# board.net
KiCad netlist of a schematic drawn in EAGLE
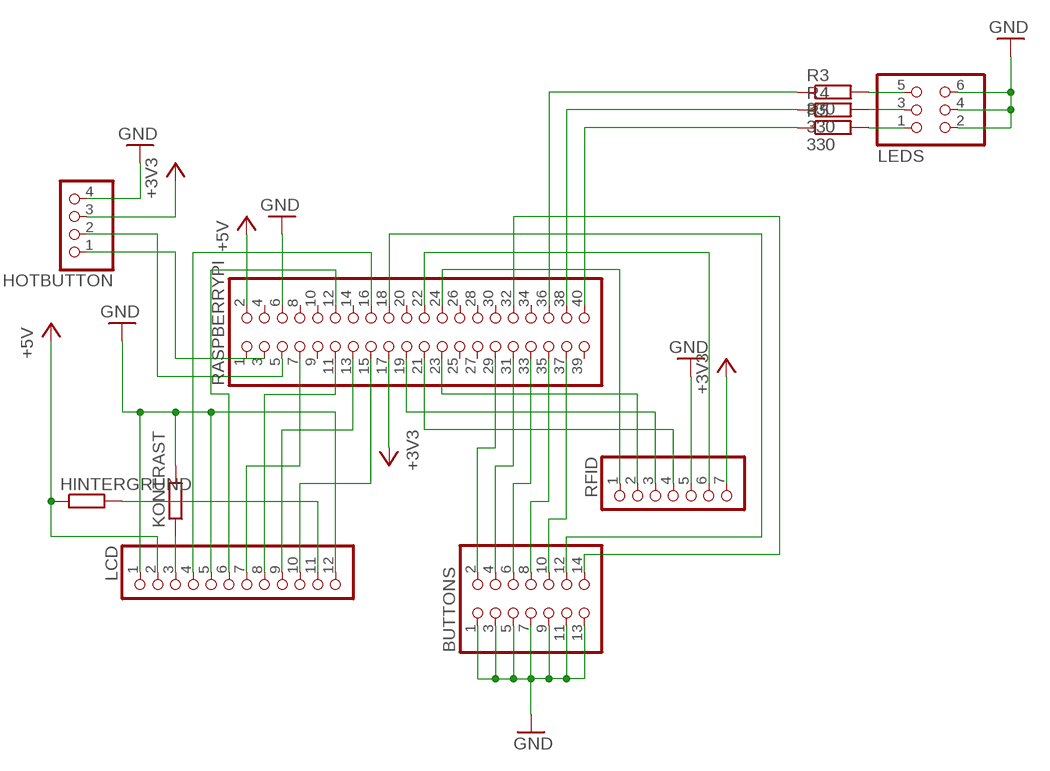
[diagram p0: schematic, sheet 1]

(export (version "E")
  (design (tool "Eeschema 10.0.6"))
  (components
    (comp (ref "BUTTONS")
      (value "PINHD-2X7")
      (footprint "eagle-import:2X07")
      (libsource (lib "eagle-import") (part "PINHD-2X7"))
    )
    (comp (ref "HINTERGRUND")
      (value "R-EU_0207/10")
      (footprint "eagle-import:0207_10")
      (libsource (lib "eagle-import") (part "R-EU_0207/10"))
    )
    (comp (ref "HOTBUTTON")
      (value "PINHD-1X4")
      (footprint "eagle-import:1X04")
      (libsource (lib "eagle-import") (part "PINHD-1X4"))
    )
    (comp (ref "KONTRAST")
      (value "R-EU_0207/10")
      (footprint "eagle-import:0207_10")
      (libsource (lib "eagle-import") (part "R-EU_0207/10"))
    )
    (comp (ref "LCD")
      (value "PINHD-1X12")
      (footprint "eagle-import:1X12")
      (libsource (lib "eagle-import") (part "PINHD-1X12"))
    )
    (comp (ref "LEDS")
      (value "PINHD-2X3")
      (footprint "eagle-import:2X03")
      (libsource (lib "eagle-import") (part "PINHD-2X3"))
    )
    (comp (ref "R3")
      (value "330")
      (footprint "eagle-import:0207_10")
      (libsource (lib "eagle-import") (part "R-EU_0207/10"))
    )
    (comp (ref "R4")
      (value "330")
      (footprint "eagle-import:0207_10")
      (libsource (lib "eagle-import") (part "R-EU_0207/10"))
    )
    (comp (ref "R5")
      (value "330")
      (footprint "eagle-import:0207_10")
      (libsource (lib "eagle-import") (part "R-EU_0207/10"))
    )
    (comp (ref "RASPBERRYPI")
      (value "PINHD-2X20")
      (footprint "eagle-import:2X20")
      (libsource (lib "eagle-import") (part "PINHD-2X20"))
    )
    (comp (ref "RFID")
      (value "PINHD-1X7")
      (footprint "eagle-import:1X07")
      (libsource (lib "eagle-import") (part "PINHD-1X7"))
    )
  )
  (nets
    (net (code "1") (name "+3V3") (class "Default")
      (node (ref "HOTBUTTON") (pin "3") (pinfunction "3_3") (pintype "passive"))
      (node (ref "RASPBERRYPI") (pin "17") (pinfunction "17_17") (pintype "passive"))
      (node (ref "RFID") (pin "7") (pinfunction "7_7") (pintype "passive"))
    )
    (net (code "2") (name "+5V") (class "Default")
      (node (ref "HINTERGRUND") (pin "1") (pinfunction "1_1") (pintype "passive"))
      (node (ref "LCD") (pin "2") (pinfunction "2_2") (pintype "passive"))
      (node (ref "RASPBERRYPI") (pin "2") (pinfunction "2_2") (pintype "passive"))
    )
    (net (code "3") (name "GND") (class "Default")
      (node (ref "BUTTONS") (pin "1") (pinfunction "1_1") (pintype "passive"))
      (node (ref "BUTTONS") (pin "11") (pinfunction "11_11") (pintype "passive"))
      (node (ref "BUTTONS") (pin "13") (pinfunction "13_13") (pintype "passive"))
      (node (ref "BUTTONS") (pin "3") (pinfunction "3_3") (pintype "passive"))
      (node (ref "BUTTONS") (pin "5") (pinfunction "5_5") (pintype "passive"))
      (node (ref "BUTTONS") (pin "7") (pinfunction "7_7") (pintype "passive"))
      (node (ref "BUTTONS") (pin "9") (pinfunction "9_9") (pintype "passive"))
      (node (ref "HOTBUTTON") (pin "4") (pinfunction "4_4") (pintype "passive"))
      (node (ref "KONTRAST") (pin "2") (pinfunction "2_2") (pintype "passive"))
      (node (ref "LCD") (pin "1") (pinfunction "1_1") (pintype "passive"))
      (node (ref "LCD") (pin "12") (pinfunction "12_12") (pintype "passive"))
      (node (ref "LCD") (pin "5") (pinfunction "5_5") (pintype "passive"))
      (node (ref "LEDS") (pin "2") (pinfunction "2_2") (pintype "passive"))
      (node (ref "LEDS") (pin "4") (pinfunction "4_4") (pintype "passive"))
      (node (ref "LEDS") (pin "6") (pinfunction "6_6") (pintype "passive"))
      (node (ref "RASPBERRYPI") (pin "6") (pinfunction "6_6") (pintype "passive"))
      (node (ref "RFID") (pin "5") (pinfunction "5_5") (pintype "passive"))
    )
    (net (code "4") (name "Net-(BUTTONS-Pad2)") (class "Default")
      (node (ref "BUTTONS") (pin "2") (pinfunction "2_2") (pintype "passive"))
      (node (ref "RASPBERRYPI") (pin "29") (pinfunction "29_29") (pintype "passive"))
    )
    (net (code "5") (name "Net-(BUTTONS-Pad4)") (class "Default")
      (node (ref "BUTTONS") (pin "4") (pinfunction "4_4") (pintype "passive"))
      (node (ref "RASPBERRYPI") (pin "31") (pinfunction "31_31") (pintype "passive"))
    )
    (net (code "6") (name "Net-(BUTTONS-Pad6)") (class "Default")
      (node (ref "BUTTONS") (pin "6") (pinfunction "6_6") (pintype "passive"))
      (node (ref "RASPBERRYPI") (pin "33") (pinfunction "33_33") (pintype "passive"))
    )
    (net (code "7") (name "Net-(BUTTONS-Pad8)") (class "Default")
      (node (ref "BUTTONS") (pin "8") (pinfunction "8_8") (pintype "passive"))
      (node (ref "RASPBERRYPI") (pin "35") (pinfunction "35_35") (pintype "passive"))
    )
    (net (code "8") (name "Net-(BUTTONS-Pad10)") (class "Default")
      (node (ref "BUTTONS") (pin "10") (pinfunction "10_10") (pintype "passive"))
      (node (ref "RASPBERRYPI") (pin "37") (pinfunction "37_37") (pintype "passive"))
    )
    (net (code "9") (name "Net-(BUTTONS-Pad12)") (class "Default")
      (node (ref "BUTTONS") (pin "12") (pinfunction "12_12") (pintype "passive"))
      (node (ref "RASPBERRYPI") (pin "18") (pinfunction "18_18") (pintype "passive"))
    )
    (net (code "10") (name "Net-(BUTTONS-Pad14)") (class "Default")
      (node (ref "BUTTONS") (pin "14") (pinfunction "14_14") (pintype "passive"))
      (node (ref "RASPBERRYPI") (pin "32") (pinfunction "32_32") (pintype "passive"))
    )
    (net (code "11") (name "Net-(HINTERGRUND-Pad2)") (class "Default")
      (node (ref "HINTERGRUND") (pin "2") (pinfunction "2_2") (pintype "passive"))
      (node (ref "LCD") (pin "11") (pinfunction "11_11") (pintype "passive"))
    )
    (net (code "12") (name "Net-(HOTBUTTON-Pad1)") (class "Default")
      (node (ref "HOTBUTTON") (pin "1") (pinfunction "1_1") (pintype "passive"))
      (node (ref "RASPBERRYPI") (pin "3") (pinfunction "3_3") (pintype "passive"))
    )
    (net (code "13") (name "Net-(HOTBUTTON-Pad2)") (class "Default")
      (node (ref "HOTBUTTON") (pin "2") (pinfunction "2_2") (pintype "passive"))
      (node (ref "RASPBERRYPI") (pin "5") (pinfunction "5_5") (pintype "passive"))
    )
    (net (code "14") (name "Net-(KONTRAST-Pad1)") (class "Default")
      (node (ref "KONTRAST") (pin "1") (pinfunction "1_1") (pintype "passive"))
      (node (ref "LCD") (pin "3") (pinfunction "3_3") (pintype "passive"))
    )
    (net (code "15") (name "Net-(LCD-Pad4)") (class "Default")
      (node (ref "LCD") (pin "4") (pinfunction "4_4") (pintype "passive"))
      (node (ref "RASPBERRYPI") (pin "16") (pinfunction "16_16") (pintype "passive"))
    )
    (net (code "16") (name "Net-(LCD-Pad6)") (class "Default")
      (node (ref "LCD") (pin "6") (pinfunction "6_6") (pintype "passive"))
      (node (ref "RASPBERRYPI") (pin "12") (pinfunction "12_12") (pintype "passive"))
    )
    (net (code "17") (name "Net-(LCD-Pad7)") (class "Default")
      (node (ref "LCD") (pin "7") (pinfunction "7_7") (pintype "passive"))
      (node (ref "RASPBERRYPI") (pin "7") (pinfunction "7_7") (pintype "passive"))
    )
    (net (code "18") (name "Net-(LCD-Pad8)") (class "Default")
      (node (ref "LCD") (pin "8") (pinfunction "8_8") (pintype "passive"))
      (node (ref "RASPBERRYPI") (pin "11") (pinfunction "11_11") (pintype "passive"))
    )
    (net (code "19") (name "Net-(LCD-Pad9)") (class "Default")
      (node (ref "LCD") (pin "9") (pinfunction "9_9") (pintype "passive"))
      (node (ref "RASPBERRYPI") (pin "13") (pinfunction "13_13") (pintype "passive"))
    )
    (net (code "20") (name "Net-(LCD-Pad10)") (class "Default")
      (node (ref "LCD") (pin "10") (pinfunction "10_10") (pintype "passive"))
      (node (ref "RASPBERRYPI") (pin "15") (pinfunction "15_15") (pintype "passive"))
    )
    (net (code "21") (name "Net-(LEDS-Pad1)") (class "Default")
      (node (ref "LEDS") (pin "1") (pinfunction "1_1") (pintype "passive"))
      (node (ref "R5") (pin "2") (pinfunction "2_2") (pintype "passive"))
    )
    (net (code "22") (name "Net-(LEDS-Pad3)") (class "Default")
      (node (ref "LEDS") (pin "3") (pinfunction "3_3") (pintype "passive"))
      (node (ref "R4") (pin "2") (pinfunction "2_2") (pintype "passive"))
    )
    (net (code "23") (name "Net-(LEDS-Pad5)") (class "Default")
      (node (ref "LEDS") (pin "5") (pinfunction "5_5") (pintype "passive"))
      (node (ref "R3") (pin "2") (pinfunction "2_2") (pintype "passive"))
    )
    (net (code "24") (name "Net-(R3-Pad1)") (class "Default")
      (node (ref "R3") (pin "1") (pinfunction "1_1") (pintype "passive"))
      (node (ref "RASPBERRYPI") (pin "36") (pinfunction "36_36") (pintype "passive"))
    )
    (net (code "25") (name "Net-(R4-Pad1)") (class "Default")
      (node (ref "R4") (pin "1") (pinfunction "1_1") (pintype "passive"))
      (node (ref "RASPBERRYPI") (pin "38") (pinfunction "38_38") (pintype "passive"))
    )
    (net (code "26") (name "Net-(R5-Pad1)") (class "Default")
      (node (ref "R5") (pin "1") (pinfunction "1_1") (pintype "passive"))
      (node (ref "RASPBERRYPI") (pin "40") (pinfunction "40_40") (pintype "passive"))
    )
    (net (code "27") (name "Net-(RASPBERRYPI-Pad19)") (class "Default")
      (node (ref "RASPBERRYPI") (pin "19") (pinfunction "19_19") (pintype "passive"))
      (node (ref "RFID") (pin "3") (pinfunction "3_3") (pintype "passive"))
    )
    (net (code "28") (name "Net-(RASPBERRYPI-Pad21)") (class "Default")
      (node (ref "RASPBERRYPI") (pin "21") (pinfunction "21_21") (pintype "passive"))
      (node (ref "RFID") (pin "4") (pinfunction "4_4") (pintype "passive"))
    )
    (net (code "29") (name "Net-(RASPBERRYPI-Pad22)") (class "Default")
      (node (ref "RASPBERRYPI") (pin "22") (pinfunction "22_22") (pintype "passive"))
      (node (ref "RFID") (pin "6") (pinfunction "6_6") (pintype "passive"))
    )
    (net (code "30") (name "Net-(RASPBERRYPI-Pad23)") (class "Default")
      (node (ref "RASPBERRYPI") (pin "23") (pinfunction "23_23") (pintype "passive"))
      (node (ref "RFID") (pin "2") (pinfunction "2_2") (pintype "passive"))
    )
    (net (code "31") (name "Net-(RASPBERRYPI-Pad24)") (class "Default")
      (node (ref "RASPBERRYPI") (pin "24") (pinfunction "24_24") (pintype "passive"))
      (node (ref "RFID") (pin "1") (pinfunction "1_1") (pintype "passive"))
    )
    (net (code "32") (name "unconnected-(RASPBERRYPI-Pad1)") (class "Default")
      (node (ref "RASPBERRYPI") (pin "1") (pinfunction "1_1") (pintype "passive"))
    )
    (net (code "33") (name "unconnected-(RASPBERRYPI-Pad4)") (class "Default")
      (node (ref "RASPBERRYPI") (pin "4") (pinfunction "4_4") (pintype "passive"))
    )
    (net (code "34") (name "unconnected-(RASPBERRYPI-Pad8)") (class "Default")
      (node (ref "RASPBERRYPI") (pin "8") (pinfunction "8_8") (pintype "passive"))
    )
    (net (code "35") (name "unconnected-(RASPBERRYPI-Pad9)") (class "Default")
      (node (ref "RASPBERRYPI") (pin "9") (pinfunction "9_9") (pintype "passive"))
    )
    (net (code "36") (name "unconnected-(RASPBERRYPI-Pad10)") (class "Default")
      (node (ref "RASPBERRYPI") (pin "10") (pinfunction "10_10") (pintype "passive"))
    )
    (net (code "37") (name "unconnected-(RASPBERRYPI-Pad14)") (class "Default")
      (node (ref "RASPBERRYPI") (pin "14") (pinfunction "14_14") (pintype "passive"))
    )
    (net (code "38") (name "unconnected-(RASPBERRYPI-Pad20)") (class "Default")
      (node (ref "RASPBERRYPI") (pin "20") (pinfunction "20_20") (pintype "passive"))
    )
    (net (code "39") (name "unconnected-(RASPBERRYPI-Pad25)") (class "Default")
      (node (ref "RASPBERRYPI") (pin "25") (pinfunction "25_25") (pintype "passive"))
    )
    (net (code "40") (name "unconnected-(RASPBERRYPI-Pad26)") (class "Default")
      (node (ref "RASPBERRYPI") (pin "26") (pinfunction "26_26") (pintype "passive"))
    )
    (net (code "41") (name "unconnected-(RASPBERRYPI-Pad27)") (class "Default")
      (node (ref "RASPBERRYPI") (pin "27") (pinfunction "27_27") (pintype "passive"))
    )
    (net (code "42") (name "unconnected-(RASPBERRYPI-Pad28)") (class "Default")
      (node (ref "RASPBERRYPI") (pin "28") (pinfunction "28_28") (pintype "passive"))
    )
    (net (code "43") (name "unconnected-(RASPBERRYPI-Pad30)") (class "Default")
      (node (ref "RASPBERRYPI") (pin "30") (pinfunction "30_30") (pintype "passive"))
    )
    (net (code "44") (name "unconnected-(RASPBERRYPI-Pad34)") (class "Default")
      (node (ref "RASPBERRYPI") (pin "34") (pinfunction "34_34") (pintype "passive"))
    )
    (net (code "45") (name "unconnected-(RASPBERRYPI-Pad39)") (class "Default")
      (node (ref "RASPBERRYPI") (pin "39") (pinfunction "39_39") (pintype "passive"))
    )
  )
)
